# FPGA_U1_Auto.net
KiCad netlist of a schematic drawn in Altium Designer
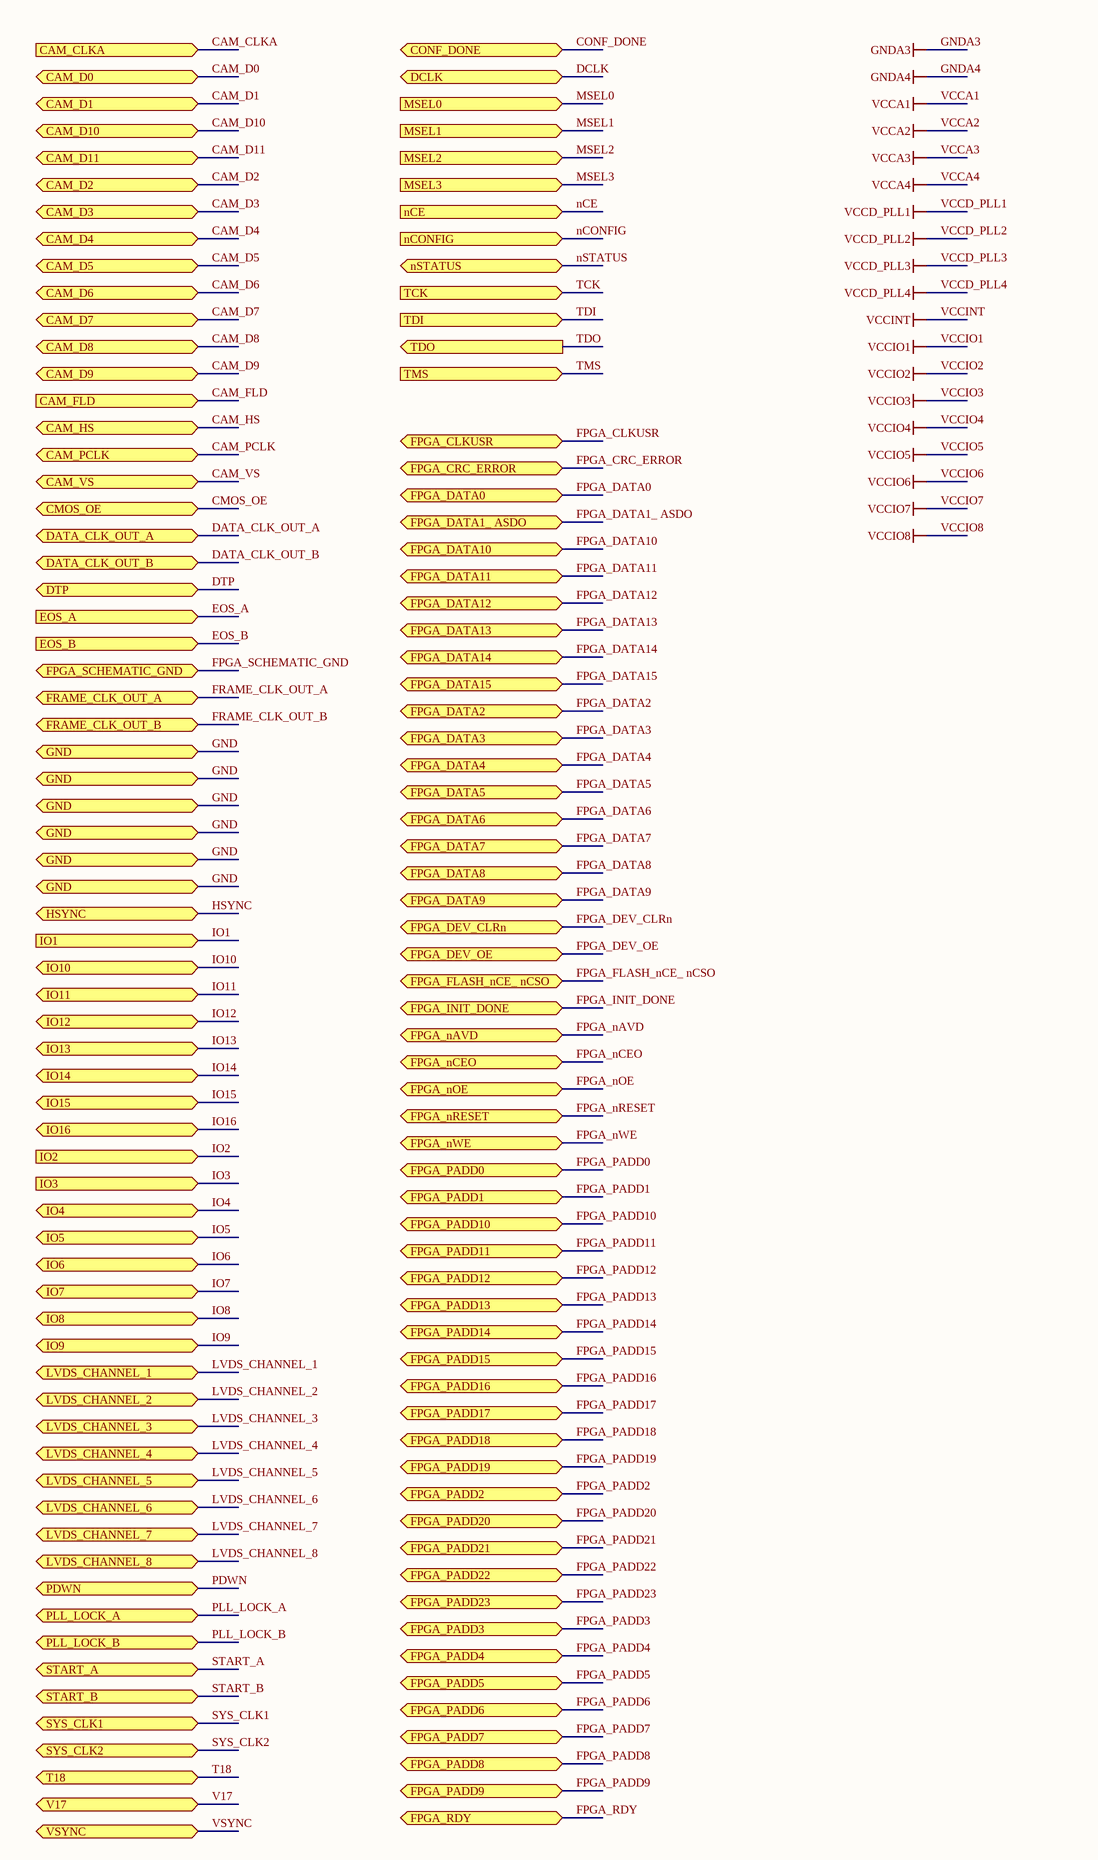
[diagram p0: FPGA_U1_Auto.SchDoc, top left]
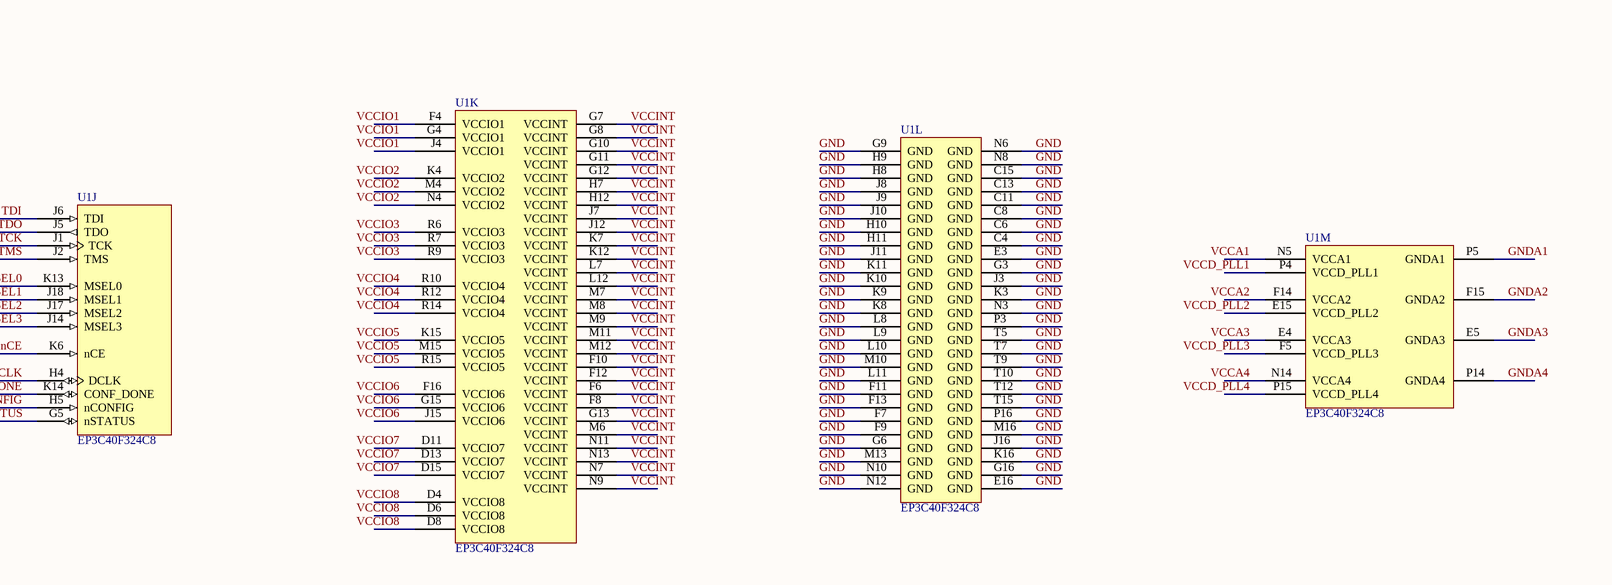
[diagram p1: FPGA_U1_Auto.SchDoc, top middle]
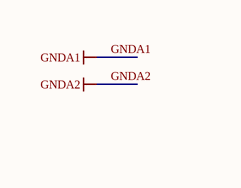
[diagram p2: FPGA_U1_Auto.SchDoc, bottom left]
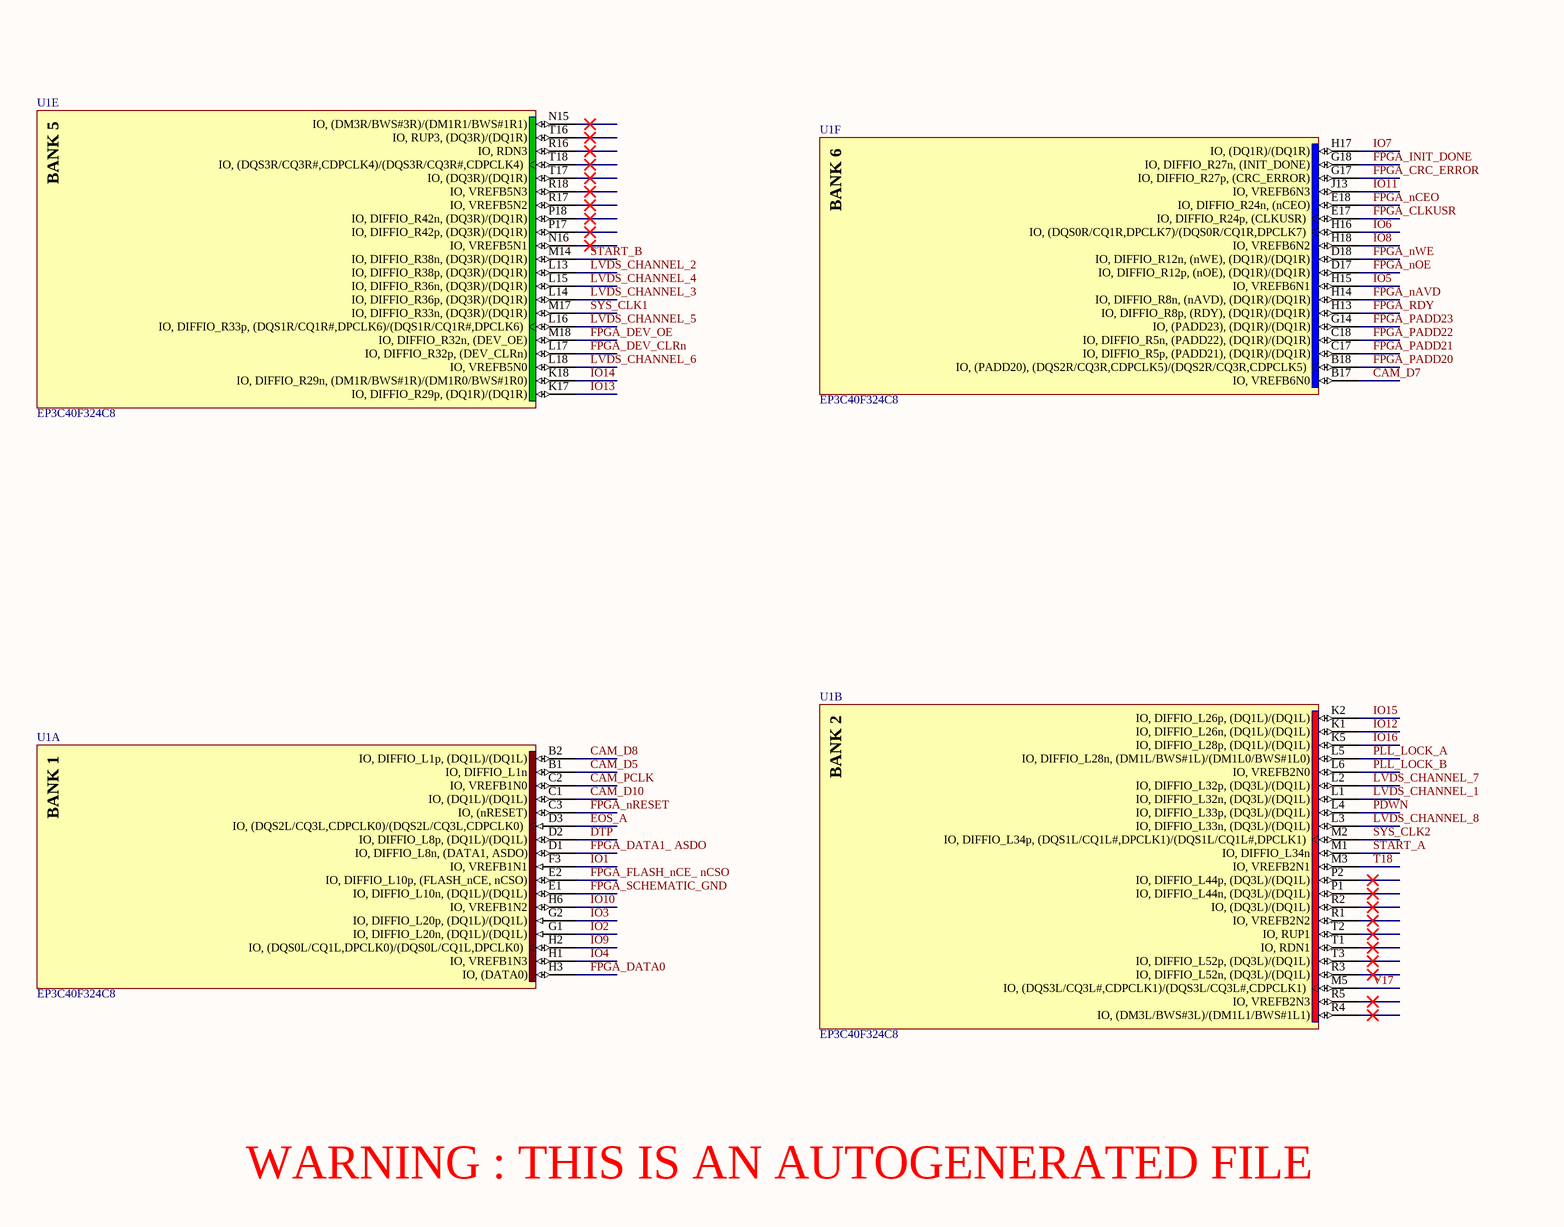
[diagram p3: FPGA_U1_Auto.SchDoc, bottom middle]
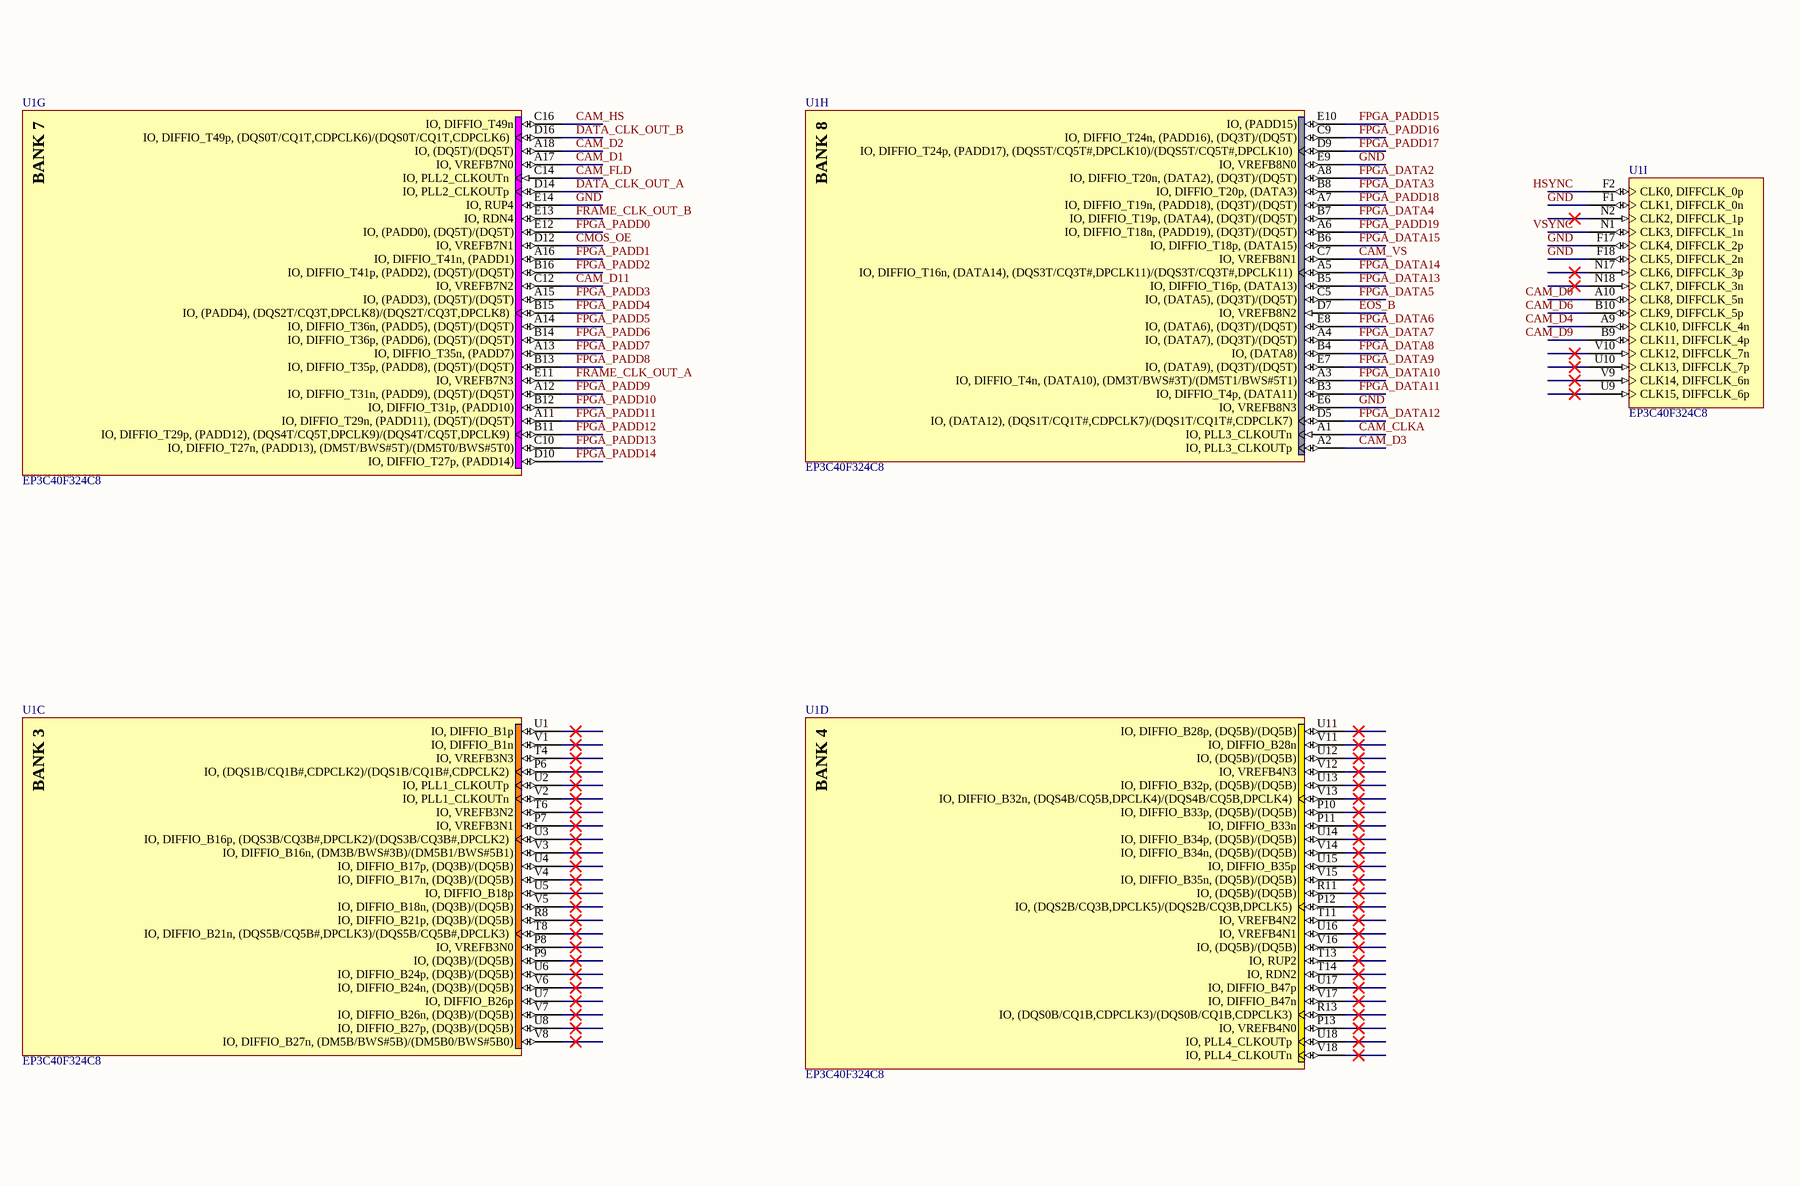
[diagram p4: FPGA_U1_Auto.SchDoc, bottom right]

(export (version "E")
  (design (tool "Eeschema 10.0.6"))
  (components
    (comp (ref "U1")
      (value "EP3C40F324C8")
      (footprint "FBGA324")
      (description "Cyclone III Family FPGA, 195 I/O Pins, 4 PLLs, 324-Pin FBGA, Speed Grade 8, Commercial Grade")
      (fields (field (name "PUBLISHER") "Altium Limited"))
      (libsource (lib "Altera Cyclone III") (part "EP3C40F324C8"))
    )
  )
  (nets
    (net (code "1") (name "/CAM_CLKA") (class "Default")
      (node (ref "U1") (pin "A1") (pinfunction "IO,_PLL3_CLKOUTn_A1") (pintype "bidirectional"))
    )
    (net (code "2") (name "/CAM_D0") (class "Default")
      (node (ref "U1") (pin "A10") (pinfunction "CLK8,_DIFFCLK_5n_A10") (pintype "input"))
    )
    (net (code "3") (name "/CAM_D1") (class "Default")
      (node (ref "U1") (pin "A17") (pinfunction "IO,_VREFB7N0_A17") (pintype "bidirectional"))
    )
    (net (code "4") (name "/CAM_D2") (class "Default")
      (node (ref "U1") (pin "A18") (pinfunction "IO,_(DQ5T)/(DQ5T)_A18") (pintype "bidirectional"))
    )
    (net (code "5") (name "/CAM_D3") (class "Default")
      (node (ref "U1") (pin "A2") (pinfunction "IO,_PLL3_CLKOUTp_A2") (pintype "bidirectional"))
    )
    (net (code "6") (name "/CAM_D4") (class "Default")
      (node (ref "U1") (pin "A9") (pinfunction "CLK10,_DIFFCLK_4n_A9") (pintype "input"))
    )
    (net (code "7") (name "/CAM_D5") (class "Default")
      (node (ref "U1") (pin "B1") (pinfunction "IO,_DIFFIO_L1n_B1") (pintype "bidirectional"))
    )
    (net (code "8") (name "/CAM_D6") (class "Default")
      (node (ref "U1") (pin "B10") (pinfunction "CLK9,_DIFFCLK_5p_B10") (pintype "input"))
    )
    (net (code "9") (name "/CAM_D7") (class "Default")
      (node (ref "U1") (pin "B17") (pinfunction "IO,_VREFB6N0_B17") (pintype "bidirectional"))
    )
    (net (code "10") (name "/CAM_D8") (class "Default")
      (node (ref "U1") (pin "B2") (pinfunction "IO,_DIFFIO_L1p,_(DQ1L)/(DQ1L)_B2") (pintype "bidirectional"))
    )
    (net (code "11") (name "/CAM_D9") (class "Default")
      (node (ref "U1") (pin "B9") (pinfunction "CLK11,_DIFFCLK_4p_B9") (pintype "input"))
    )
    (net (code "12") (name "/CAM_D10") (class "Default")
      (node (ref "U1") (pin "C1") (pinfunction "IO,_(DQ1L)/(DQ1L)_C1") (pintype "bidirectional"))
    )
    (net (code "13") (name "/CAM_D11") (class "Default")
      (node (ref "U1") (pin "C12") (pinfunction "IO,_VREFB7N2_C12") (pintype "bidirectional"))
    )
    (net (code "14") (name "/CAM_FLD") (class "Default")
      (node (ref "U1") (pin "C14") (pinfunction "IO,_PLL2_CLKOUTn_C14") (pintype "bidirectional"))
    )
    (net (code "15") (name "/CAM_HS") (class "Default")
      (node (ref "U1") (pin "C16") (pinfunction "IO,_DIFFIO_T49n_C16") (pintype "bidirectional"))
    )
    (net (code "16") (name "/CAM_PCLK") (class "Default")
      (node (ref "U1") (pin "C2") (pinfunction "IO,_VREFB1N0_C2") (pintype "bidirectional"))
    )
    (net (code "17") (name "/CAM_VS") (class "Default")
      (node (ref "U1") (pin "C7") (pinfunction "IO,_VREFB8N1_C7") (pintype "bidirectional"))
    )
    (net (code "18") (name "/CMOS_OE") (class "Default")
      (node (ref "U1") (pin "D12") (pinfunction "IO,_VREFB7N1_D12") (pintype "bidirectional"))
    )
    (net (code "19") (name "/CONF_DONE") (class "Default")
      (node (ref "U1") (pin "K14") (pinfunction "CONF_DONE_K14") (pintype "bidirectional"))
    )
    (net (code "20") (name "/DATA_CLK_OUT_A") (class "Default")
      (node (ref "U1") (pin "D14") (pinfunction "IO,_PLL2_CLKOUTp_D14") (pintype "bidirectional"))
    )
    (net (code "21") (name "/DATA_CLK_OUT_B") (class "Default")
      (node (ref "U1") (pin "D16") (pinfunction "IO,_DIFFIO_T49p,_(DQS0T/CQ1T,CDPCLK6)/(DQS0T/CQ1T,CDPCLK6)_D16") (pintype "bidirectional"))
    )
    (net (code "22") (name "/DCLK") (class "Default")
      (node (ref "U1") (pin "H4") (pinfunction "DCLK_H4") (pintype "bidirectional"))
    )
    (net (code "23") (name "/DTP") (class "Default")
      (node (ref "U1") (pin "D2") (pinfunction "IO,_DIFFIO_L8p,_(DQ1L)/(DQ1L)_D2") (pintype "bidirectional"))
    )
    (net (code "24") (name "/EOS_A") (class "Default")
      (node (ref "U1") (pin "D3") (pinfunction "IO,_(DQS2L/CQ3L,CDPCLK0)/(DQS2L/CQ3L,CDPCLK0)_D3") (pintype "bidirectional"))
    )
    (net (code "25") (name "/EOS_B") (class "Default")
      (node (ref "U1") (pin "D7") (pinfunction "IO,_VREFB8N2_D7") (pintype "bidirectional"))
    )
    (net (code "26") (name "/FPGA_CLKUSR") (class "Default")
      (node (ref "U1") (pin "E17") (pinfunction "IO,_DIFFIO_R24p,_(CLKUSR)_E17") (pintype "bidirectional"))
    )
    (net (code "27") (name "/FPGA_CRC_ERROR") (class "Default")
      (node (ref "U1") (pin "G17") (pinfunction "IO,_DIFFIO_R27p,_(CRC_ERROR)_G17") (pintype "bidirectional"))
    )
    (net (code "28") (name "/FPGA_DATA0") (class "Default")
      (node (ref "U1") (pin "H3") (pinfunction "IO,_(DATA0)_H3") (pintype "bidirectional"))
    )
    (net (code "29") (name "/FPGA_DATA1_ ASDO") (class "Default")
      (node (ref "U1") (pin "D1") (pinfunction "IO,_DIFFIO_L8n,_(DATA1,_ASDO)_D1") (pintype "bidirectional"))
    )
    (net (code "30") (name "/FPGA_DATA2") (class "Default")
      (node (ref "U1") (pin "A8") (pinfunction "IO,_DIFFIO_T20n,_(DATA2),_(DQ3T)/(DQ5T)_A8") (pintype "bidirectional"))
    )
    (net (code "31") (name "/FPGA_DATA3") (class "Default")
      (node (ref "U1") (pin "B8") (pinfunction "IO,_DIFFIO_T20p,_(DATA3)_B8") (pintype "bidirectional"))
    )
    (net (code "32") (name "/FPGA_DATA4") (class "Default")
      (node (ref "U1") (pin "B7") (pinfunction "IO,_DIFFIO_T19p,_(DATA4),_(DQ3T)/(DQ5T)_B7") (pintype "bidirectional"))
    )
    (net (code "33") (name "/FPGA_DATA5") (class "Default")
      (node (ref "U1") (pin "C5") (pinfunction "IO,_(DATA5),_(DQ3T)/(DQ5T)_C5") (pintype "bidirectional"))
    )
    (net (code "34") (name "/FPGA_DATA6") (class "Default")
      (node (ref "U1") (pin "E8") (pinfunction "IO,_(DATA6),_(DQ3T)/(DQ5T)_E8") (pintype "bidirectional"))
    )
    (net (code "35") (name "/FPGA_DATA7") (class "Default")
      (node (ref "U1") (pin "A4") (pinfunction "IO,_(DATA7),_(DQ3T)/(DQ5T)_A4") (pintype "bidirectional"))
    )
    (net (code "36") (name "/FPGA_DATA8") (class "Default")
      (node (ref "U1") (pin "B4") (pinfunction "IO,_(DATA8)_B4") (pintype "bidirectional"))
    )
    (net (code "37") (name "/FPGA_DATA9") (class "Default")
      (node (ref "U1") (pin "E7") (pinfunction "IO,_(DATA9),_(DQ3T)/(DQ5T)_E7") (pintype "bidirectional"))
    )
    (net (code "38") (name "/FPGA_DATA10") (class "Default")
      (node (ref "U1") (pin "A3") (pinfunction "IO,_DIFFIO_T4n,_(DATA10),_(DM3T/BWS#3T)/(DM5T1/BWS#5T1)_A3") (pintype "bidirectional"))
    )
    (net (code "39") (name "/FPGA_DATA11") (class "Default")
      (node (ref "U1") (pin "B3") (pinfunction "IO,_DIFFIO_T4p,_(DATA11)_B3") (pintype "bidirectional"))
    )
    (net (code "40") (name "/FPGA_DATA12") (class "Default")
      (node (ref "U1") (pin "D5") (pinfunction "IO,_(DATA12),_(DQS1T/CQ1T#,CDPCLK7)/(DQS1T/CQ1T#,CDPCLK7)_D5") (pintype "bidirectional"))
    )
    (net (code "41") (name "/FPGA_DATA13") (class "Default")
      (node (ref "U1") (pin "B5") (pinfunction "IO,_DIFFIO_T16p,_(DATA13)_B5") (pintype "bidirectional"))
    )
    (net (code "42") (name "/FPGA_DATA14") (class "Default")
      (node (ref "U1") (pin "A5") (pinfunction "IO,_DIFFIO_T16n,_(DATA14),_(DQS3T/CQ3T#,DPCLK11)/(DQS3T/CQ3T#,DPCLK11)_A5") (pintype "bidirectional"))
    )
    (net (code "43") (name "/FPGA_DATA15") (class "Default")
      (node (ref "U1") (pin "B6") (pinfunction "IO,_DIFFIO_T18p,_(DATA15)_B6") (pintype "bidirectional"))
    )
    (net (code "44") (name "/FPGA_DEV_CLRn") (class "Default")
      (node (ref "U1") (pin "L17") (pinfunction "IO,_DIFFIO_R32p,_(DEV_CLRn)_L17") (pintype "bidirectional"))
    )
    (net (code "45") (name "/FPGA_DEV_OE") (class "Default")
      (node (ref "U1") (pin "M18") (pinfunction "IO,_DIFFIO_R32n,_(DEV_OE)_M18") (pintype "bidirectional"))
    )
    (net (code "46") (name "/FPGA_FLASH_nCE_ nCSO") (class "Default")
      (node (ref "U1") (pin "E2") (pinfunction "IO,_DIFFIO_L10p,_(FLASH_nCE,_nCSO)_E2") (pintype "bidirectional"))
    )
    (net (code "47") (name "/FPGA_INIT_DONE") (class "Default")
      (node (ref "U1") (pin "G18") (pinfunction "IO,_DIFFIO_R27n,_(INIT_DONE)_G18") (pintype "bidirectional"))
    )
    (net (code "48") (name "/FPGA_PADD0") (class "Default")
      (node (ref "U1") (pin "E12") (pinfunction "IO,_(PADD0),_(DQ5T)/(DQ5T)_E12") (pintype "bidirectional"))
    )
    (net (code "49") (name "/FPGA_PADD1") (class "Default")
      (node (ref "U1") (pin "A16") (pinfunction "IO,_DIFFIO_T41n,_(PADD1)_A16") (pintype "bidirectional"))
    )
    (net (code "50") (name "/FPGA_PADD2") (class "Default")
      (node (ref "U1") (pin "B16") (pinfunction "IO,_DIFFIO_T41p,_(PADD2),_(DQ5T)/(DQ5T)_B16") (pintype "bidirectional"))
    )
    (net (code "51") (name "/FPGA_PADD3") (class "Default")
      (node (ref "U1") (pin "A15") (pinfunction "IO,_(PADD3),_(DQ5T)/(DQ5T)_A15") (pintype "bidirectional"))
    )
    (net (code "52") (name "/FPGA_PADD4") (class "Default")
      (node (ref "U1") (pin "B15") (pinfunction "IO,_(PADD4),_(DQS2T/CQ3T,DPCLK8)/(DQS2T/CQ3T,DPCLK8)_B15") (pintype "bidirectional"))
    )
    (net (code "53") (name "/FPGA_PADD5") (class "Default")
      (node (ref "U1") (pin "A14") (pinfunction "IO,_DIFFIO_T36n,_(PADD5),_(DQ5T)/(DQ5T)_A14") (pintype "bidirectional"))
    )
    (net (code "54") (name "/FPGA_PADD6") (class "Default")
      (node (ref "U1") (pin "B14") (pinfunction "IO,_DIFFIO_T36p,_(PADD6),_(DQ5T)/(DQ5T)_B14") (pintype "bidirectional"))
    )
    (net (code "55") (name "/FPGA_PADD7") (class "Default")
      (node (ref "U1") (pin "A13") (pinfunction "IO,_DIFFIO_T35n,_(PADD7)_A13") (pintype "bidirectional"))
    )
    (net (code "56") (name "/FPGA_PADD8") (class "Default")
      (node (ref "U1") (pin "B13") (pinfunction "IO,_DIFFIO_T35p,_(PADD8),_(DQ5T)/(DQ5T)_B13") (pintype "bidirectional"))
    )
    (net (code "57") (name "/FPGA_PADD9") (class "Default")
      (node (ref "U1") (pin "A12") (pinfunction "IO,_DIFFIO_T31n,_(PADD9),_(DQ5T)/(DQ5T)_A12") (pintype "bidirectional"))
    )
    (net (code "58") (name "/FPGA_PADD10") (class "Default")
      (node (ref "U1") (pin "B12") (pinfunction "IO,_DIFFIO_T31p,_(PADD10)_B12") (pintype "bidirectional"))
    )
    (net (code "59") (name "/FPGA_PADD11") (class "Default")
      (node (ref "U1") (pin "A11") (pinfunction "IO,_DIFFIO_T29n,_(PADD11),_(DQ5T)/(DQ5T)_A11") (pintype "bidirectional"))
    )
    (net (code "60") (name "/FPGA_PADD12") (class "Default")
      (node (ref "U1") (pin "B11") (pinfunction "IO,_DIFFIO_T29p,_(PADD12),_(DQS4T/CQ5T,DPCLK9)/(DQS4T/CQ5T,DPCLK9)_B11") (pintype "bidirectional"))
    )
    (net (code "61") (name "/FPGA_PADD13") (class "Default")
      (node (ref "U1") (pin "C10") (pinfunction "IO,_DIFFIO_T27n,_(PADD13),_(DM5T/BWS#5T)/(DM5T0/BWS#5T0)_C10") (pintype "bidirectional"))
    )
    (net (code "62") (name "/FPGA_PADD14") (class "Default")
      (node (ref "U1") (pin "D10") (pinfunction "IO,_DIFFIO_T27p,_(PADD14)_D10") (pintype "bidirectional"))
    )
    (net (code "63") (name "/FPGA_PADD15") (class "Default")
      (node (ref "U1") (pin "E10") (pinfunction "IO,_(PADD15)_E10") (pintype "bidirectional"))
    )
    (net (code "64") (name "/FPGA_PADD16") (class "Default")
      (node (ref "U1") (pin "C9") (pinfunction "IO,_DIFFIO_T24n,_(PADD16),_(DQ3T)/(DQ5T)_C9") (pintype "bidirectional"))
    )
    (net (code "65") (name "/FPGA_PADD17") (class "Default")
      (node (ref "U1") (pin "D9") (pinfunction "IO,_DIFFIO_T24p,_(PADD17),_(DQS5T/CQ5T#,DPCLK10)/(DQS5T/CQ5T#,DPCLK10)_D9") (pintype "bidirectional"))
    )
    (net (code "66") (name "/FPGA_PADD18") (class "Default")
      (node (ref "U1") (pin "A7") (pinfunction "IO,_DIFFIO_T19n,_(PADD18),_(DQ3T)/(DQ5T)_A7") (pintype "bidirectional"))
    )
    (net (code "67") (name "/FPGA_PADD19") (class "Default")
      (node (ref "U1") (pin "A6") (pinfunction "IO,_DIFFIO_T18n,_(PADD19),_(DQ3T)/(DQ5T)_A6") (pintype "bidirectional"))
    )
    (net (code "68") (name "/FPGA_PADD20") (class "Default")
      (node (ref "U1") (pin "B18") (pinfunction "IO,_(PADD20),_(DQS2R/CQ3R,CDPCLK5)/(DQS2R/CQ3R,CDPCLK5)_B18") (pintype "bidirectional"))
    )
    (net (code "69") (name "/FPGA_PADD21") (class "Default")
      (node (ref "U1") (pin "C17") (pinfunction "IO,_DIFFIO_R5p,_(PADD21),_(DQ1R)/(DQ1R)_C17") (pintype "bidirectional"))
    )
    (net (code "70") (name "/FPGA_PADD22") (class "Default")
      (node (ref "U1") (pin "C18") (pinfunction "IO,_DIFFIO_R5n,_(PADD22),_(DQ1R)/(DQ1R)_C18") (pintype "bidirectional"))
    )
    (net (code "71") (name "/FPGA_PADD23") (class "Default")
      (node (ref "U1") (pin "G14") (pinfunction "IO,_(PADD23),_(DQ1R)/(DQ1R)_G14") (pintype "bidirectional"))
    )
    (net (code "72") (name "/FPGA_RDY") (class "Default")
      (node (ref "U1") (pin "H13") (pinfunction "IO,_DIFFIO_R8p,_(RDY),_(DQ1R)/(DQ1R)_H13") (pintype "bidirectional"))
    )
    (net (code "73") (name "/FPGA_SCHEMATIC_GND") (class "Default")
      (node (ref "U1") (pin "E1") (pinfunction "IO,_DIFFIO_L10n,_(DQ1L)/(DQ1L)_E1") (pintype "bidirectional"))
    )
    (net (code "74") (name "/FPGA_nAVD") (class "Default")
      (node (ref "U1") (pin "H14") (pinfunction "IO,_DIFFIO_R8n,_(nAVD),_(DQ1R)/(DQ1R)_H14") (pintype "bidirectional"))
    )
    (net (code "75") (name "/FPGA_nCEO") (class "Default")
      (node (ref "U1") (pin "E18") (pinfunction "IO,_DIFFIO_R24n,_(nCEO)_E18") (pintype "bidirectional"))
    )
    (net (code "76") (name "/FPGA_nOE") (class "Default")
      (node (ref "U1") (pin "D17") (pinfunction "IO,_DIFFIO_R12p,_(nOE),_(DQ1R)/(DQ1R)_D17") (pintype "bidirectional"))
    )
    (net (code "77") (name "/FPGA_nRESET") (class "Default")
      (node (ref "U1") (pin "C3") (pinfunction "IO,_(nRESET)_C3") (pintype "bidirectional"))
    )
    (net (code "78") (name "/FPGA_nWE") (class "Default")
      (node (ref "U1") (pin "D18") (pinfunction "IO,_DIFFIO_R12n,_(nWE),_(DQ1R)/(DQ1R)_D18") (pintype "bidirectional"))
    )
    (net (code "79") (name "/FRAME_CLK_OUT_A") (class "Default")
      (node (ref "U1") (pin "E11") (pinfunction "IO,_VREFB7N3_E11") (pintype "bidirectional"))
    )
    (net (code "80") (name "/FRAME_CLK_OUT_B") (class "Default")
      (node (ref "U1") (pin "E13") (pinfunction "IO,_RDN4_E13") (pintype "bidirectional"))
    )
    (net (code "81") (name "/GND") (class "Default")
      (node (ref "U1") (pin "C11") (pinfunction "GND_C11") (pintype "power_in"))
      (node (ref "U1") (pin "C13") (pinfunction "GND_C13") (pintype "power_in"))
      (node (ref "U1") (pin "C15") (pinfunction "GND_C15") (pintype "power_in"))
      (node (ref "U1") (pin "C4") (pinfunction "GND_C4") (pintype "power_in"))
      (node (ref "U1") (pin "C6") (pinfunction "GND_C6") (pintype "power_in"))
      (node (ref "U1") (pin "C8") (pinfunction "GND_C8") (pintype "power_in"))
      (node (ref "U1") (pin "E14") (pinfunction "IO,_RUP4_E14") (pintype "bidirectional"))
      (node (ref "U1") (pin "E16") (pinfunction "GND_E16") (pintype "power_in"))
      (node (ref "U1") (pin "E3") (pinfunction "GND_E3") (pintype "power_in"))
      (node (ref "U1") (pin "E6") (pinfunction "IO,_VREFB8N3_E6") (pintype "bidirectional"))
      (node (ref "U1") (pin "E9") (pinfunction "IO,_VREFB8N0_E9") (pintype "bidirectional"))
      (node (ref "U1") (pin "F1") (pinfunction "CLK1,_DIFFCLK_0n_F1") (pintype "input"))
      (node (ref "U1") (pin "F11") (pinfunction "GND_F11") (pintype "power_in"))
      (node (ref "U1") (pin "F13") (pinfunction "GND_F13") (pintype "power_in"))
      (node (ref "U1") (pin "F17") (pinfunction "CLK4,_DIFFCLK_2p_F17") (pintype "input"))
      (node (ref "U1") (pin "F18") (pinfunction "CLK5,_DIFFCLK_2n_F18") (pintype "input"))
      (node (ref "U1") (pin "F7") (pinfunction "GND_F7") (pintype "power_in"))
      (node (ref "U1") (pin "F9") (pinfunction "GND_F9") (pintype "power_in"))
      (node (ref "U1") (pin "G16") (pinfunction "GND_G16") (pintype "power_in"))
      (node (ref "U1") (pin "G3") (pinfunction "GND_G3") (pintype "power_in"))
      (node (ref "U1") (pin "G6") (pinfunction "GND_G6") (pintype "power_in"))
      (node (ref "U1") (pin "G9") (pinfunction "GND_G9") (pintype "power_in"))
      (node (ref "U1") (pin "H10") (pinfunction "GND_H10") (pintype "power_in"))
      (node (ref "U1") (pin "H11") (pinfunction "GND_H11") (pintype "power_in"))
      (node (ref "U1") (pin "H8") (pinfunction "GND_H8") (pintype "power_in"))
      (node (ref "U1") (pin "H9") (pinfunction "GND_H9") (pintype "power_in"))
      (node (ref "U1") (pin "J10") (pinfunction "GND_J10") (pintype "power_in"))
      (node (ref "U1") (pin "J11") (pinfunction "GND_J11") (pintype "power_in"))
      (node (ref "U1") (pin "J16") (pinfunction "GND_J16") (pintype "power_in"))
      (node (ref "U1") (pin "J3") (pinfunction "GND_J3") (pintype "power_in"))
      (node (ref "U1") (pin "J8") (pinfunction "GND_J8") (pintype "power_in"))
      (node (ref "U1") (pin "J9") (pinfunction "GND_J9") (pintype "power_in"))
      (node (ref "U1") (pin "K10") (pinfunction "GND_K10") (pintype "power_in"))
      (node (ref "U1") (pin "K11") (pinfunction "GND_K11") (pintype "power_in"))
      (node (ref "U1") (pin "K16") (pinfunction "GND_K16") (pintype "power_in"))
      (node (ref "U1") (pin "K3") (pinfunction "GND_K3") (pintype "power_in"))
      (node (ref "U1") (pin "K8") (pinfunction "GND_K8") (pintype "power_in"))
      (node (ref "U1") (pin "K9") (pinfunction "GND_K9") (pintype "power_in"))
      (node (ref "U1") (pin "L10") (pinfunction "GND_L10") (pintype "power_in"))
      (node (ref "U1") (pin "L11") (pinfunction "GND_L11") (pintype "power_in"))
      (node (ref "U1") (pin "L8") (pinfunction "GND_L8") (pintype "power_in"))
      (node (ref "U1") (pin "L9") (pinfunction "GND_L9") (pintype "power_in"))
      (node (ref "U1") (pin "M10") (pinfunction "GND_M10") (pintype "power_in"))
      (node (ref "U1") (pin "M13") (pinfunction "GND_M13") (pintype "power_in"))
      (node (ref "U1") (pin "M16") (pinfunction "GND_M16") (pintype "power_in"))
      (node (ref "U1") (pin "N10") (pinfunction "GND_N10") (pintype "power_in"))
      (node (ref "U1") (pin "N12") (pinfunction "GND_N12") (pintype "power_in"))
      (node (ref "U1") (pin "N3") (pinfunction "GND_N3") (pintype "power_in"))
      (node (ref "U1") (pin "N6") (pinfunction "GND_N6") (pintype "power_in"))
      (node (ref "U1") (pin "N8") (pinfunction "GND_N8") (pintype "power_in"))
      (node (ref "U1") (pin "P16") (pinfunction "GND_P16") (pintype "power_in"))
      (node (ref "U1") (pin "P3") (pinfunction "GND_P3") (pintype "power_in"))
      (node (ref "U1") (pin "T10") (pinfunction "GND_T10") (pintype "power_in"))
      (node (ref "U1") (pin "T12") (pinfunction "GND_T12") (pintype "power_in"))
      (node (ref "U1") (pin "T15") (pinfunction "GND_T15") (pintype "power_in"))
      (node (ref "U1") (pin "T5") (pinfunction "GND_T5") (pintype "power_in"))
      (node (ref "U1") (pin "T7") (pinfunction "GND_T7") (pintype "power_in"))
      (node (ref "U1") (pin "T9") (pinfunction "GND_T9") (pintype "power_in"))
    )
    (net (code "82") (name "/HSYNC") (class "Default")
      (node (ref "U1") (pin "F2") (pinfunction "CLK0,_DIFFCLK_0p_F2") (pintype "input"))
    )
    (net (code "83") (name "/IO1") (class "Default")
      (node (ref "U1") (pin "F3") (pinfunction "IO,_VREFB1N1_F3") (pintype "bidirectional"))
    )
    (net (code "84") (name "/IO2") (class "Default")
      (node (ref "U1") (pin "G1") (pinfunction "IO,_DIFFIO_L20n,_(DQ1L)/(DQ1L)_G1") (pintype "bidirectional"))
    )
    (net (code "85") (name "/IO3") (class "Default")
      (node (ref "U1") (pin "G2") (pinfunction "IO,_DIFFIO_L20p,_(DQ1L)/(DQ1L)_G2") (pintype "bidirectional"))
    )
    (net (code "86") (name "/IO4") (class "Default")
      (node (ref "U1") (pin "H1") (pinfunction "IO,_VREFB1N3_H1") (pintype "bidirectional"))
    )
    (net (code "87") (name "/IO5") (class "Default")
      (node (ref "U1") (pin "H15") (pinfunction "IO,_VREFB6N1_H15") (pintype "bidirectional"))
    )
    (net (code "88") (name "/IO6") (class "Default")
      (node (ref "U1") (pin "H16") (pinfunction "IO,_(DQS0R/CQ1R,DPCLK7)/(DQS0R/CQ1R,DPCLK7)_H16") (pintype "bidirectional"))
    )
    (net (code "89") (name "/IO7") (class "Default")
      (node (ref "U1") (pin "H17") (pinfunction "IO,_(DQ1R)/(DQ1R)_H17") (pintype "bidirectional"))
    )
    (net (code "90") (name "/IO8") (class "Default")
      (node (ref "U1") (pin "H18") (pinfunction "IO,_VREFB6N2_H18") (pintype "bidirectional"))
    )
    (net (code "91") (name "/IO9") (class "Default")
      (node (ref "U1") (pin "H2") (pinfunction "IO,_(DQS0L/CQ1L,DPCLK0)/(DQS0L/CQ1L,DPCLK0)_H2") (pintype "bidirectional"))
    )
    (net (code "92") (name "/IO10") (class "Default")
      (node (ref "U1") (pin "H6") (pinfunction "IO,_VREFB1N2_H6") (pintype "bidirectional"))
    )
    (net (code "93") (name "/IO11") (class "Default")
      (node (ref "U1") (pin "J13") (pinfunction "IO,_VREFB6N3_J13") (pintype "bidirectional"))
    )
    (net (code "94") (name "/IO12") (class "Default")
      (node (ref "U1") (pin "K1") (pinfunction "IO,_DIFFIO_L26n,_(DQ1L)/(DQ1L)_K1") (pintype "bidirectional"))
    )
    (net (code "95") (name "/IO13") (class "Default")
      (node (ref "U1") (pin "K17") (pinfunction "IO,_DIFFIO_R29p,_(DQ1R)/(DQ1R)_K17") (pintype "bidirectional"))
    )
    (net (code "96") (name "/IO14") (class "Default")
      (node (ref "U1") (pin "K18") (pinfunction "IO,_DIFFIO_R29n,_(DM1R/BWS#1R)/(DM1R0/BWS#1R0)_K18") (pintype "bidirectional"))
    )
    (net (code "97") (name "/IO15") (class "Default")
      (node (ref "U1") (pin "K2") (pinfunction "IO,_DIFFIO_L26p,_(DQ1L)/(DQ1L)_K2") (pintype "bidirectional"))
    )
    (net (code "98") (name "/IO16") (class "Default")
      (node (ref "U1") (pin "K5") (pinfunction "IO,_DIFFIO_L28p,_(DQ1L)/(DQ1L)_K5") (pintype "bidirectional"))
    )
    (net (code "99") (name "/LVDS_CHANNEL_1") (class "Default")
      (node (ref "U1") (pin "L1") (pinfunction "IO,_DIFFIO_L32n,_(DQ3L)/(DQ1L)_L1") (pintype "bidirectional"))
    )
    (net (code "100") (name "/LVDS_CHANNEL_2") (class "Default")
      (node (ref "U1") (pin "L13") (pinfunction "IO,_DIFFIO_R38p,_(DQ3R)/(DQ1R)_L13") (pintype "bidirectional"))
    )
    (net (code "101") (name "/LVDS_CHANNEL_3") (class "Default")
      (node (ref "U1") (pin "L14") (pinfunction "IO,_DIFFIO_R36p,_(DQ3R)/(DQ1R)_L14") (pintype "bidirectional"))
    )
    (net (code "102") (name "/LVDS_CHANNEL_4") (class "Default")
      (node (ref "U1") (pin "L15") (pinfunction "IO,_DIFFIO_R36n,_(DQ3R)/(DQ1R)_L15") (pintype "bidirectional"))
    )
    (net (code "103") (name "/LVDS_CHANNEL_5") (class "Default")
      (node (ref "U1") (pin "L16") (pinfunction "IO,_DIFFIO_R33p,_(DQS1R/CQ1R#,DPCLK6)/(DQS1R/CQ1R#,DPCLK6)_L16") (pintype "bidirectional"))
    )
    (net (code "104") (name "/LVDS_CHANNEL_6") (class "Default")
      (node (ref "U1") (pin "L18") (pinfunction "IO,_VREFB5N0_L18") (pintype "bidirectional"))
    )
    (net (code "105") (name "/LVDS_CHANNEL_7") (class "Default")
      (node (ref "U1") (pin "L2") (pinfunction "IO,_DIFFIO_L32p,_(DQ3L)/(DQ1L)_L2") (pintype "bidirectional"))
    )
    (net (code "106") (name "/LVDS_CHANNEL_8") (class "Default")
      (node (ref "U1") (pin "L3") (pinfunction "IO,_DIFFIO_L33n,_(DQ3L)/(DQ1L)_L3") (pintype "bidirectional"))
    )
    (net (code "107") (name "/MSEL0") (class "Default")
      (node (ref "U1") (pin "K13") (pinfunction "MSEL0_K13") (pintype "input"))
    )
    (net (code "108") (name "/MSEL1") (class "Default")
      (node (ref "U1") (pin "J18") (pinfunction "MSEL1_J18") (pintype "input"))
    )
    (net (code "109") (name "/MSEL2") (class "Default")
      (node (ref "U1") (pin "J17") (pinfunction "MSEL2_J17") (pintype "input"))
    )
    (net (code "110") (name "/MSEL3") (class "Default")
      (node (ref "U1") (pin "J14") (pinfunction "MSEL3_J14") (pintype "input"))
    )
    (net (code "111") (name "/PDWN") (class "Default")
      (node (ref "U1") (pin "L4") (pinfunction "IO,_DIFFIO_L33p,_(DQ3L)/(DQ1L)_L4") (pintype "bidirectional"))
    )
    (net (code "112") (name "/PLL_LOCK_A") (class "Default")
      (node (ref "U1") (pin "L5") (pinfunction "IO,_DIFFIO_L28n,_(DM1L/BWS#1L)/(DM1L0/BWS#1L0)_L5") (pintype "bidirectional"))
    )
    (net (code "113") (name "/PLL_LOCK_B") (class "Default")
      (node (ref "U1") (pin "L6") (pinfunction "IO,_VREFB2N0_L6") (pintype "bidirectional"))
    )
    (net (code "114") (name "/START_A") (class "Default")
      (node (ref "U1") (pin "M1") (pinfunction "IO,_DIFFIO_L34n_M1") (pintype "bidirectional"))
    )
    (net (code "115") (name "/START_B") (class "Default")
      (node (ref "U1") (pin "M14") (pinfunction "IO,_DIFFIO_R38n,_(DQ3R)/(DQ1R)_M14") (pintype "bidirectional"))
    )
    (net (code "116") (name "/SYS_CLK1") (class "Default")
      (node (ref "U1") (pin "M17") (pinfunction "IO,_DIFFIO_R33n,_(DQ3R)/(DQ1R)_M17") (pintype "bidirectional"))
    )
    (net (code "117") (name "/SYS_CLK2") (class "Default")
      (node (ref "U1") (pin "M2") (pinfunction "IO,_DIFFIO_L34p,_(DQS1L/CQ1L#,DPCLK1)/(DQS1L/CQ1L#,DPCLK1)_M2") (pintype "bidirectional"))
    )
    (net (code "118") (name "/T18") (class "Default")
      (node (ref "U1") (pin "M3") (pinfunction "IO,_VREFB2N1_M3") (pintype "bidirectional"))
    )
    (net (code "119") (name "/TCK") (class "Default")
      (node (ref "U1") (pin "J1") (pinfunction "TCK_J1") (pintype "input"))
    )
    (net (code "120") (name "/TDI") (class "Default")
      (node (ref "U1") (pin "J6") (pinfunction "TDI_J6") (pintype "input"))
    )
    (net (code "121") (name "/TDO") (class "Default")
      (node (ref "U1") (pin "J5") (pinfunction "TDO_J5") (pintype "output"))
    )
    (net (code "122") (name "/TMS") (class "Default")
      (node (ref "U1") (pin "J2") (pinfunction "TMS_J2") (pintype "input"))
    )
    (net (code "123") (name "/V17") (class "Default")
      (node (ref "U1") (pin "M5") (pinfunction "IO,_(DQS3L/CQ3L#,CDPCLK1)/(DQS3L/CQ3L#,CDPCLK1)_M5") (pintype "bidirectional"))
    )
    (net (code "124") (name "/VSYNC") (class "Default")
      (node (ref "U1") (pin "N1") (pinfunction "CLK3,_DIFFCLK_1n_N1") (pintype "input"))
    )
    (net (code "125") (name "/nCE") (class "Default")
      (node (ref "U1") (pin "K6") (pinfunction "nCE_K6") (pintype "input"))
    )
    (net (code "126") (name "/nCONFIG") (class "Default")
      (node (ref "U1") (pin "H5") (pinfunction "nCONFIG_H5") (pintype "input"))
    )
    (net (code "127") (name "/nSTATUS") (class "Default")
      (node (ref "U1") (pin "G5") (pinfunction "nSTATUS_G5") (pintype "bidirectional"))
    )
    (net (code "128") (name "GNDA1") (class "Default")
      (node (ref "U1") (pin "P5") (pinfunction "GNDA1_P5") (pintype "power_in"))
    )
    (net (code "129") (name "GNDA2") (class "Default")
      (node (ref "U1") (pin "F15") (pinfunction "GNDA2_F15") (pintype "power_in"))
    )
    (net (code "130") (name "GNDA3") (class "Default")
      (node (ref "U1") (pin "E5") (pinfunction "GNDA3_E5") (pintype "power_in"))
    )
    (net (code "131") (name "GNDA4") (class "Default")
      (node (ref "U1") (pin "P14") (pinfunction "GNDA4_P14") (pintype "power_in"))
    )
    (net (code "132") (name "VCCA1") (class "Default")
      (node (ref "U1") (pin "N5") (pinfunction "VCCA1_N5") (pintype "power_in"))
    )
    (net (code "133") (name "VCCA2") (class "Default")
      (node (ref "U1") (pin "F14") (pinfunction "VCCA2_F14") (pintype "power_in"))
    )
    (net (code "134") (name "VCCA3") (class "Default")
      (node (ref "U1") (pin "E4") (pinfunction "VCCA3_E4") (pintype "power_in"))
    )
    (net (code "135") (name "VCCA4") (class "Default")
      (node (ref "U1") (pin "N14") (pinfunction "VCCA4_N14") (pintype "power_in"))
    )
    (net (code "136") (name "VCCD_PLL1") (class "Default")
      (node (ref "U1") (pin "P4") (pinfunction "VCCD_PLL1_P4") (pintype "power_in"))
    )
    (net (code "137") (name "VCCD_PLL2") (class "Default")
      (node (ref "U1") (pin "E15") (pinfunction "VCCD_PLL2_E15") (pintype "power_in"))
    )
    (net (code "138") (name "VCCD_PLL3") (class "Default")
      (node (ref "U1") (pin "F5") (pinfunction "VCCD_PLL3_F5") (pintype "power_in"))
    )
    (net (code "139") (name "VCCD_PLL4") (class "Default")
      (node (ref "U1") (pin "P15") (pinfunction "VCCD_PLL4_P15") (pintype "power_in"))
    )
    (net (code "140") (name "VCCINT") (class "Default")
      (node (ref "U1") (pin "F10") (pinfunction "VCCINT_F10") (pintype "power_in"))
      (node (ref "U1") (pin "F12") (pinfunction "VCCINT_F12") (pintype "power_in"))
      (node (ref "U1") (pin "F6") (pinfunction "VCCINT_F6") (pintype "power_in"))
      (node (ref "U1") (pin "F8") (pinfunction "VCCINT_F8") (pintype "power_in"))
      (node (ref "U1") (pin "G10") (pinfunction "VCCINT_G10") (pintype "power_in"))
      (node (ref "U1") (pin "G11") (pinfunction "VCCINT_G11") (pintype "power_in"))
      (node (ref "U1") (pin "G12") (pinfunction "VCCINT_G12") (pintype "power_in"))
      (node (ref "U1") (pin "G13") (pinfunction "VCCINT_G13") (pintype "power_in"))
      (node (ref "U1") (pin "G7") (pinfunction "VCCINT_G7") (pintype "power_in"))
      (node (ref "U1") (pin "G8") (pinfunction "VCCINT_G8") (pintype "power_in"))
      (node (ref "U1") (pin "H12") (pinfunction "VCCINT_H12") (pintype "power_in"))
      (node (ref "U1") (pin "H7") (pinfunction "VCCINT_H7") (pintype "power_in"))
      (node (ref "U1") (pin "J12") (pinfunction "VCCINT_J12") (pintype "power_in"))
      (node (ref "U1") (pin "J7") (pinfunction "VCCINT_J7") (pintype "power_in"))
      (node (ref "U1") (pin "K12") (pinfunction "VCCINT_K12") (pintype "power_in"))
      (node (ref "U1") (pin "K7") (pinfunction "VCCINT_K7") (pintype "power_in"))
      (node (ref "U1") (pin "L12") (pinfunction "VCCINT_L12") (pintype "power_in"))
      (node (ref "U1") (pin "L7") (pinfunction "VCCINT_L7") (pintype "power_in"))
      (node (ref "U1") (pin "M11") (pinfunction "VCCINT_M11") (pintype "power_in"))
      (node (ref "U1") (pin "M12") (pinfunction "VCCINT_M12") (pintype "power_in"))
      (node (ref "U1") (pin "M6") (pinfunction "VCCINT_M6") (pintype "power_in"))
      (node (ref "U1") (pin "M7") (pinfunction "VCCINT_M7") (pintype "power_in"))
      (node (ref "U1") (pin "M8") (pinfunction "VCCINT_M8") (pintype "power_in"))
      (node (ref "U1") (pin "M9") (pinfunction "VCCINT_M9") (pintype "power_in"))
      (node (ref "U1") (pin "N11") (pinfunction "VCCINT_N11") (pintype "power_in"))
      (node (ref "U1") (pin "N13") (pinfunction "VCCINT_N13") (pintype "power_in"))
      (node (ref "U1") (pin "N7") (pinfunction "VCCINT_N7") (pintype "power_in"))
      (node (ref "U1") (pin "N9") (pinfunction "VCCINT_N9") (pintype "power_in"))
    )
    (net (code "141") (name "VCCIO1") (class "Default")
      (node (ref "U1") (pin "F4") (pinfunction "VCCIO1_F4") (pintype "power_in"))
      (node (ref "U1") (pin "G4") (pinfunction "VCCIO1_G4") (pintype "power_in"))
      (node (ref "U1") (pin "J4") (pinfunction "VCCIO1_J4") (pintype "power_in"))
    )
    (net (code "142") (name "VCCIO2") (class "Default")
      (node (ref "U1") (pin "K4") (pinfunction "VCCIO2_K4") (pintype "power_in"))
      (node (ref "U1") (pin "M4") (pinfunction "VCCIO2_M4") (pintype "power_in"))
      (node (ref "U1") (pin "N4") (pinfunction "VCCIO2_N4") (pintype "power_in"))
    )
    (net (code "143") (name "VCCIO3") (class "Default")
      (node (ref "U1") (pin "R6") (pinfunction "VCCIO3_R6") (pintype "power_in"))
      (node (ref "U1") (pin "R7") (pinfunction "VCCIO3_R7") (pintype "power_in"))
      (node (ref "U1") (pin "R9") (pinfunction "VCCIO3_R9") (pintype "power_in"))
    )
    (net (code "144") (name "VCCIO4") (class "Default")
      (node (ref "U1") (pin "R10") (pinfunction "VCCIO4_R10") (pintype "power_in"))
      (node (ref "U1") (pin "R12") (pinfunction "VCCIO4_R12") (pintype "power_in"))
      (node (ref "U1") (pin "R14") (pinfunction "VCCIO4_R14") (pintype "power_in"))
    )
    (net (code "145") (name "VCCIO5") (class "Default")
      (node (ref "U1") (pin "K15") (pinfunction "VCCIO5_K15") (pintype "power_in"))
      (node (ref "U1") (pin "M15") (pinfunction "VCCIO5_M15") (pintype "power_in"))
      (node (ref "U1") (pin "R15") (pinfunction "VCCIO5_R15") (pintype "power_in"))
    )
    (net (code "146") (name "VCCIO6") (class "Default")
      (node (ref "U1") (pin "F16") (pinfunction "VCCIO6_F16") (pintype "power_in"))
      (node (ref "U1") (pin "G15") (pinfunction "VCCIO6_G15") (pintype "power_in"))
      (node (ref "U1") (pin "J15") (pinfunction "VCCIO6_J15") (pintype "power_in"))
    )
    (net (code "147") (name "VCCIO7") (class "Default")
      (node (ref "U1") (pin "D11") (pinfunction "VCCIO7_D11") (pintype "power_in"))
      (node (ref "U1") (pin "D13") (pinfunction "VCCIO7_D13") (pintype "power_in"))
      (node (ref "U1") (pin "D15") (pinfunction "VCCIO7_D15") (pintype "power_in"))
    )
    (net (code "148") (name "VCCIO8") (class "Default")
      (node (ref "U1") (pin "D4") (pinfunction "VCCIO8_D4") (pintype "power_in"))
      (node (ref "U1") (pin "D6") (pinfunction "VCCIO8_D6") (pintype "power_in"))
      (node (ref "U1") (pin "D8") (pinfunction "VCCIO8_D8") (pintype "power_in"))
    )
    (net (code "149") (name "unconnected-(U1B-IO,_(DM3L{slash}BWS#3L){slash}(DM1L1{slash}BWS#1L1)-PadR4)") (class "Default")
      (node (ref "U1") (pin "R4") (pinfunction "IO,_(DM3L/BWS#3L)/(DM1L1/BWS#1L1)_R4") (pintype "bidirectional"))
    )
    (net (code "150") (name "unconnected-(U1B-IO,_(DQ3L){slash}(DQ1L)-PadR2)") (class "Default")
      (node (ref "U1") (pin "R2") (pinfunction "IO,_(DQ3L)/(DQ1L)_R2") (pintype "bidirectional"))
    )
    (net (code "151") (name "unconnected-(U1B-IO,_DIFFIO_L44n,_(DQ3L){slash}(DQ1L)-PadP1)") (class "Default")
      (node (ref "U1") (pin "P1") (pinfunction "IO,_DIFFIO_L44n,_(DQ3L)/(DQ1L)_P1") (pintype "bidirectional"))
    )
    (net (code "152") (name "unconnected-(U1B-IO,_DIFFIO_L44p,_(DQ3L){slash}(DQ1L)-PadP2)") (class "Default")
      (node (ref "U1") (pin "P2") (pinfunction "IO,_DIFFIO_L44p,_(DQ3L)/(DQ1L)_P2") (pintype "bidirectional"))
    )
    (net (code "153") (name "unconnected-(U1B-IO,_DIFFIO_L52n,_(DQ3L){slash}(DQ1L)-PadR3)") (class "Default")
      (node (ref "U1") (pin "R3") (pinfunction "IO,_DIFFIO_L52n,_(DQ3L)/(DQ1L)_R3") (pintype "bidirectional"))
    )
    (net (code "154") (name "unconnected-(U1B-IO,_DIFFIO_L52p,_(DQ3L){slash}(DQ1L)-PadT3)") (class "Default")
      (node (ref "U1") (pin "T3") (pinfunction "IO,_DIFFIO_L52p,_(DQ3L)/(DQ1L)_T3") (pintype "bidirectional"))
    )
    (net (code "155") (name "unconnected-(U1B-IO,_RDN1-PadT1)") (class "Default")
      (node (ref "U1") (pin "T1") (pinfunction "IO,_RDN1_T1") (pintype "bidirectional"))
    )
    (net (code "156") (name "unconnected-(U1B-IO,_RUP1-PadT2)") (class "Default")
      (node (ref "U1") (pin "T2") (pinfunction "IO,_RUP1_T2") (pintype "bidirectional"))
    )
    (net (code "157") (name "unconnected-(U1B-IO,_VREFB2N2-PadR1)") (class "Default")
      (node (ref "U1") (pin "R1") (pinfunction "IO,_VREFB2N2_R1") (pintype "bidirectional"))
    )
    (net (code "158") (name "unconnected-(U1B-IO,_VREFB2N3-PadR5)") (class "Default")
      (node (ref "U1") (pin "R5") (pinfunction "IO,_VREFB2N3_R5") (pintype "bidirectional"))
    )
    (net (code "159") (name "unconnected-(U1C-IO,_(DQ3B){slash}(DQ5B)-PadP9)") (class "Default")
      (node (ref "U1") (pin "P9") (pinfunction "IO,_(DQ3B)/(DQ5B)_P9") (pintype "bidirectional"))
    )
    (net (code "160") (name "unconnected-(U1C-IO,_(DQS1B{slash}CQ1B#,CDPCLK2){slash}(DQS1B{slash}CQ1B#,CDPCLK2)-PadP6)") (class "Default")
      (node (ref "U1") (pin "P6") (pinfunction "IO,_(DQS1B/CQ1B#,CDPCLK2)/(DQS1B/CQ1B#,CDPCLK2)_P6") (pintype "bidirectional"))
    )
    (net (code "161") (name "unconnected-(U1C-IO,_DIFFIO_B1n-PadV1)") (class "Default")
      (node (ref "U1") (pin "V1") (pinfunction "IO,_DIFFIO_B1n_V1") (pintype "bidirectional"))
    )
    (net (code "162") (name "unconnected-(U1C-IO,_DIFFIO_B1p-PadU1)") (class "Default")
      (node (ref "U1") (pin "U1") (pinfunction "IO,_DIFFIO_B1p_U1") (pintype "bidirectional"))
    )
    (net (code "163") (name "unconnected-(U1C-IO,_DIFFIO_B16n,_(DM3B{slash}BWS#3B){slash}(DM5B1{slash}BWS#5B1)-PadV3)") (class "Default")
      (node (ref "U1") (pin "V3") (pinfunction "IO,_DIFFIO_B16n,_(DM3B/BWS#3B)/(DM5B1/BWS#5B1)_V3") (pintype "bidirectional"))
    )
    (net (code "164") (name "unconnected-(U1C-IO,_DIFFIO_B16p,_(DQS3B{slash}CQ3B#,DPCLK2){slash}(DQS3B{slash}CQ3B#,DPCLK2)-PadU3)") (class "Default")
      (node (ref "U1") (pin "U3") (pinfunction "IO,_DIFFIO_B16p,_(DQS3B/CQ3B#,DPCLK2)/(DQS3B/CQ3B#,DPCLK2)_U3") (pintype "bidirectional"))
    )
    (net (code "165") (name "unconnected-(U1C-IO,_DIFFIO_B17n,_(DQ3B){slash}(DQ5B)-PadV4)") (class "Default")
      (node (ref "U1") (pin "V4") (pinfunction "IO,_DIFFIO_B17n,_(DQ3B)/(DQ5B)_V4") (pintype "bidirectional"))
    )
    (net (code "166") (name "unconnected-(U1C-IO,_DIFFIO_B17p,_(DQ3B){slash}(DQ5B)-PadU4)") (class "Default")
      (node (ref "U1") (pin "U4") (pinfunction "IO,_DIFFIO_B17p,_(DQ3B)/(DQ5B)_U4") (pintype "bidirectional"))
    )
    (net (code "167") (name "unconnected-(U1C-IO,_DIFFIO_B18n,_(DQ3B){slash}(DQ5B)-PadV5)") (class "Default")
      (node (ref "U1") (pin "V5") (pinfunction "IO,_DIFFIO_B18n,_(DQ3B)/(DQ5B)_V5") (pintype "bidirectional"))
    )
    (net (code "168") (name "unconnected-(U1C-IO,_DIFFIO_B18p-PadU5)") (class "Default")
      (node (ref "U1") (pin "U5") (pinfunction "IO,_DIFFIO_B18p_U5") (pintype "bidirectional"))
    )
    (net (code "169") (name "unconnected-(U1C-IO,_DIFFIO_B21n,_(DQS5B{slash}CQ5B#,DPCLK3){slash}(DQS5B{slash}CQ5B#,DPCLK3)-PadT8)") (class "Default")
      (node (ref "U1") (pin "T8") (pinfunction "IO,_DIFFIO_B21n,_(DQS5B/CQ5B#,DPCLK3)/(DQS5B/CQ5B#,DPCLK3)_T8") (pintype "bidirectional"))
    )
    (net (code "170") (name "unconnected-(U1C-IO,_DIFFIO_B21p,_(DQ3B){slash}(DQ5B)-PadR8)") (class "Default")
      (node (ref "U1") (pin "R8") (pinfunction "IO,_DIFFIO_B21p,_(DQ3B)/(DQ5B)_R8") (pintype "bidirectional"))
    )
    (net (code "171") (name "unconnected-(U1C-IO,_DIFFIO_B24n,_(DQ3B){slash}(DQ5B)-PadV6)") (class "Default")
      (node (ref "U1") (pin "V6") (pinfunction "IO,_DIFFIO_B24n,_(DQ3B)/(DQ5B)_V6") (pintype "bidirectional"))
    )
    (net (code "172") (name "unconnected-(U1C-IO,_DIFFIO_B24p,_(DQ3B){slash}(DQ5B)-PadU6)") (class "Default")
      (node (ref "U1") (pin "U6") (pinfunction "IO,_DIFFIO_B24p,_(DQ3B)/(DQ5B)_U6") (pintype "bidirectional"))
    )
    (net (code "173") (name "unconnected-(U1C-IO,_DIFFIO_B26n,_(DQ3B){slash}(DQ5B)-PadV7)") (class "Default")
      (node (ref "U1") (pin "V7") (pinfunction "IO,_DIFFIO_B26n,_(DQ3B)/(DQ5B)_V7") (pintype "bidirectional"))
    )
    (net (code "174") (name "unconnected-(U1C-IO,_DIFFIO_B26p-PadU7)") (class "Default")
      (node (ref "U1") (pin "U7") (pinfunction "IO,_DIFFIO_B26p_U7") (pintype "bidirectional"))
    )
    (net (code "175") (name "unconnected-(U1C-IO,_DIFFIO_B27n,_(DM5B{slash}BWS#5B){slash}(DM5B0{slash}BWS#5B0)-PadV8)") (class "Default")
      (node (ref "U1") (pin "V8") (pinfunction "IO,_DIFFIO_B27n,_(DM5B/BWS#5B)/(DM5B0/BWS#5B0)_V8") (pintype "bidirectional"))
    )
    (net (code "176") (name "unconnected-(U1C-IO,_DIFFIO_B27p,_(DQ3B){slash}(DQ5B)-PadU8)") (class "Default")
      (node (ref "U1") (pin "U8") (pinfunction "IO,_DIFFIO_B27p,_(DQ3B)/(DQ5B)_U8") (pintype "bidirectional"))
    )
    (net (code "177") (name "unconnected-(U1C-IO,_PLL1_CLKOUTn-PadV2)") (class "Default")
      (node (ref "U1") (pin "V2") (pinfunction "IO,_PLL1_CLKOUTn_V2") (pintype "bidirectional"))
    )
    (net (code "178") (name "unconnected-(U1C-IO,_PLL1_CLKOUTp-PadU2)") (class "Default")
      (node (ref "U1") (pin "U2") (pinfunction "IO,_PLL1_CLKOUTp_U2") (pintype "bidirectional"))
    )
    (net (code "179") (name "unconnected-(U1C-IO,_VREFB3N0-PadP8)") (class "Default")
      (node (ref "U1") (pin "P8") (pinfunction "IO,_VREFB3N0_P8") (pintype "bidirectional"))
    )
    (net (code "180") (name "unconnected-(U1C-IO,_VREFB3N1-PadP7)") (class "Default")
      (node (ref "U1") (pin "P7") (pinfunction "IO,_VREFB3N1_P7") (pintype "bidirectional"))
    )
    (net (code "181") (name "unconnected-(U1C-IO,_VREFB3N2-PadT6)") (class "Default")
      (node (ref "U1") (pin "T6") (pinfunction "IO,_VREFB3N2_T6") (pintype "bidirectional"))
    )
    (net (code "182") (name "unconnected-(U1C-IO,_VREFB3N3-PadT4)") (class "Default")
      (node (ref "U1") (pin "T4") (pinfunction "IO,_VREFB3N3_T4") (pintype "bidirectional"))
    )
    (net (code "183") (name "unconnected-(U1D-IO,_(DQ5B){slash}(DQ5B)-PadR11)") (class "Default")
      (node (ref "U1") (pin "R11") (pinfunction "IO,_(DQ5B)/(DQ5B)_R11") (pintype "bidirectional"))
    )
    (net (code "184") (name "unconnected-(U1D-IO,_(DQ5B){slash}(DQ5B)-PadU12)") (class "Default")
      (node (ref "U1") (pin "U12") (pinfunction "IO,_(DQ5B)/(DQ5B)_U12") (pintype "bidirectional"))
    )
    (net (code "185") (name "unconnected-(U1D-IO,_(DQ5B){slash}(DQ5B)-PadV16)") (class "Default")
      (node (ref "U1") (pin "V16") (pinfunction "IO,_(DQ5B)/(DQ5B)_V16") (pintype "bidirectional"))
    )
    (net (code "186") (name "unconnected-(U1D-IO,_(DQS0B{slash}CQ1B,CDPCLK3){slash}(DQS0B{slash}CQ1B,CDPCLK3)-PadR13)") (class "Default")
      (node (ref "U1") (pin "R13") (pinfunction "IO,_(DQS0B/CQ1B,CDPCLK3)/(DQS0B/CQ1B,CDPCLK3)_R13") (pintype "bidirectional"))
    )
    (net (code "187") (name "unconnected-(U1D-IO,_(DQS2B{slash}CQ3B,DPCLK5){slash}(DQS2B{slash}CQ3B,DPCLK5)-PadP12)") (class "Default")
      (node (ref "U1") (pin "P12") (pinfunction "IO,_(DQS2B/CQ3B,DPCLK5)/(DQS2B/CQ3B,DPCLK5)_P12") (pintype "bidirectional"))
    )
    (net (code "188") (name "unconnected-(U1D-IO,_DIFFIO_B28n-PadV11)") (class "Default")
      (node (ref "U1") (pin "V11") (pinfunction "IO,_DIFFIO_B28n_V11") (pintype "bidirectional"))
    )
    (net (code "189") (name "unconnected-(U1D-IO,_DIFFIO_B28p,_(DQ5B){slash}(DQ5B)-PadU11)") (class "Default")
      (node (ref "U1") (pin "U11") (pinfunction "IO,_DIFFIO_B28p,_(DQ5B)/(DQ5B)_U11") (pintype "bidirectional"))
    )
    (net (code "190") (name "unconnected-(U1D-IO,_DIFFIO_B32n,_(DQS4B{slash}CQ5B,DPCLK4){slash}(DQS4B{slash}CQ5B,DPCLK4)-PadV13)") (class "Default")
      (node (ref "U1") (pin "V13") (pinfunction "IO,_DIFFIO_B32n,_(DQS4B/CQ5B,DPCLK4)/(DQS4B/CQ5B,DPCLK4)_V13") (pintype "bidirectional"))
    )
    (net (code "191") (name "unconnected-(U1D-IO,_DIFFIO_B32p,_(DQ5B){slash}(DQ5B)-PadU13)") (class "Default")
      (node (ref "U1") (pin "U13") (pinfunction "IO,_DIFFIO_B32p,_(DQ5B)/(DQ5B)_U13") (pintype "bidirectional"))
    )
    (net (code "192") (name "unconnected-(U1D-IO,_DIFFIO_B33n-PadP11)") (class "Default")
      (node (ref "U1") (pin "P11") (pinfunction "IO,_DIFFIO_B33n_P11") (pintype "bidirectional"))
    )
    (net (code "193") (name "unconnected-(U1D-IO,_DIFFIO_B33p,_(DQ5B){slash}(DQ5B)-PadP10)") (class "Default")
      (node (ref "U1") (pin "P10") (pinfunction "IO,_DIFFIO_B33p,_(DQ5B)/(DQ5B)_P10") (pintype "bidirectional"))
    )
    (net (code "194") (name "unconnected-(U1D-IO,_DIFFIO_B34n,_(DQ5B){slash}(DQ5B)-PadV14)") (class "Default")
      (node (ref "U1") (pin "V14") (pinfunction "IO,_DIFFIO_B34n,_(DQ5B)/(DQ5B)_V14") (pintype "bidirectional"))
    )
    (net (code "195") (name "unconnected-(U1D-IO,_DIFFIO_B34p,_(DQ5B){slash}(DQ5B)-PadU14)") (class "Default")
      (node (ref "U1") (pin "U14") (pinfunction "IO,_DIFFIO_B34p,_(DQ5B)/(DQ5B)_U14") (pintype "bidirectional"))
    )
    (net (code "196") (name "unconnected-(U1D-IO,_DIFFIO_B35n,_(DQ5B){slash}(DQ5B)-PadV15)") (class "Default")
      (node (ref "U1") (pin "V15") (pinfunction "IO,_DIFFIO_B35n,_(DQ5B)/(DQ5B)_V15") (pintype "bidirectional"))
    )
    (net (code "197") (name "unconnected-(U1D-IO,_DIFFIO_B35p-PadU15)") (class "Default")
      (node (ref "U1") (pin "U15") (pinfunction "IO,_DIFFIO_B35p_U15") (pintype "bidirectional"))
    )
    (net (code "198") (name "unconnected-(U1D-IO,_DIFFIO_B47n-PadV17)") (class "Default")
      (node (ref "U1") (pin "V17") (pinfunction "IO,_DIFFIO_B47n_V17") (pintype "bidirectional"))
    )
    (net (code "199") (name "unconnected-(U1D-IO,_DIFFIO_B47p-PadU17)") (class "Default")
      (node (ref "U1") (pin "U17") (pinfunction "IO,_DIFFIO_B47p_U17") (pintype "bidirectional"))
    )
    (net (code "200") (name "unconnected-(U1D-IO,_PLL4_CLKOUTn-PadV18)") (class "Default")
      (node (ref "U1") (pin "V18") (pinfunction "IO,_PLL4_CLKOUTn_V18") (pintype "bidirectional"))
    )
    (net (code "201") (name "unconnected-(U1D-IO,_PLL4_CLKOUTp-PadU18)") (class "Default")
      (node (ref "U1") (pin "U18") (pinfunction "IO,_PLL4_CLKOUTp_U18") (pintype "bidirectional"))
    )
    (net (code "202") (name "unconnected-(U1D-IO,_RDN2-PadT14)") (class "Default")
      (node (ref "U1") (pin "T14") (pinfunction "IO,_RDN2_T14") (pintype "bidirectional"))
    )
    (net (code "203") (name "unconnected-(U1D-IO,_RUP2-PadT13)") (class "Default")
      (node (ref "U1") (pin "T13") (pinfunction "IO,_RUP2_T13") (pintype "bidirectional"))
    )
    (net (code "204") (name "unconnected-(U1D-IO,_VREFB4N0-PadP13)") (class "Default")
      (node (ref "U1") (pin "P13") (pinfunction "IO,_VREFB4N0_P13") (pintype "bidirectional"))
    )
    (net (code "205") (name "unconnected-(U1D-IO,_VREFB4N1-PadU16)") (class "Default")
      (node (ref "U1") (pin "U16") (pinfunction "IO,_VREFB4N1_U16") (pintype "bidirectional"))
    )
    (net (code "206") (name "unconnected-(U1D-IO,_VREFB4N2-PadT11)") (class "Default")
      (node (ref "U1") (pin "T11") (pinfunction "IO,_VREFB4N2_T11") (pintype "bidirectional"))
    )
    (net (code "207") (name "unconnected-(U1D-IO,_VREFB4N3-PadV12)") (class "Default")
      (node (ref "U1") (pin "V12") (pinfunction "IO,_VREFB4N3_V12") (pintype "bidirectional"))
    )
    (net (code "208") (name "unconnected-(U1E-IO,_(DM3R{slash}BWS#3R){slash}(DM1R1{slash}BWS#1R1)-PadN15)") (class "Default")
      (node (ref "U1") (pin "N15") (pinfunction "IO,_(DM3R/BWS#3R)/(DM1R1/BWS#1R1)_N15") (pintype "bidirectional"))
    )
    (net (code "209") (name "unconnected-(U1E-IO,_(DQ3R){slash}(DQ1R)-PadT17)") (class "Default")
      (node (ref "U1") (pin "T17") (pinfunction "IO,_(DQ3R)/(DQ1R)_T17") (pintype "bidirectional"))
    )
    (net (code "210") (name "unconnected-(U1E-IO,_(DQS3R{slash}CQ3R#,CDPCLK4){slash}(DQS3R{slash}CQ3R#,CDPCLK4)-PadT18)") (class "Default")
      (node (ref "U1") (pin "T18") (pinfunction "IO,_(DQS3R/CQ3R#,CDPCLK4)/(DQS3R/CQ3R#,CDPCLK4)_T18") (pintype "bidirectional"))
    )
    (net (code "211") (name "unconnected-(U1E-IO,_DIFFIO_R42n,_(DQ3R){slash}(DQ1R)-PadP18)") (class "Default")
      (node (ref "U1") (pin "P18") (pinfunction "IO,_DIFFIO_R42n,_(DQ3R)/(DQ1R)_P18") (pintype "bidirectional"))
    )
    (net (code "212") (name "unconnected-(U1E-IO,_DIFFIO_R42p,_(DQ3R){slash}(DQ1R)-PadP17)") (class "Default")
      (node (ref "U1") (pin "P17") (pinfunction "IO,_DIFFIO_R42p,_(DQ3R)/(DQ1R)_P17") (pintype "bidirectional"))
    )
    (net (code "213") (name "unconnected-(U1E-IO,_RDN3-PadR16)") (class "Default")
      (node (ref "U1") (pin "R16") (pinfunction "IO,_RDN3_R16") (pintype "bidirectional"))
    )
    (net (code "214") (name "unconnected-(U1E-IO,_RUP3,_(DQ3R){slash}(DQ1R)-PadT16)") (class "Default")
      (node (ref "U1") (pin "T16") (pinfunction "IO,_RUP3,_(DQ3R)/(DQ1R)_T16") (pintype "bidirectional"))
    )
    (net (code "215") (name "unconnected-(U1E-IO,_VREFB5N1-PadN16)") (class "Default")
      (node (ref "U1") (pin "N16") (pinfunction "IO,_VREFB5N1_N16") (pintype "bidirectional"))
    )
    (net (code "216") (name "unconnected-(U1E-IO,_VREFB5N2-PadR17)") (class "Default")
      (node (ref "U1") (pin "R17") (pinfunction "IO,_VREFB5N2_R17") (pintype "bidirectional"))
    )
    (net (code "217") (name "unconnected-(U1E-IO,_VREFB5N3-PadR18)") (class "Default")
      (node (ref "U1") (pin "R18") (pinfunction "IO,_VREFB5N3_R18") (pintype "bidirectional"))
    )
    (net (code "218") (name "unconnected-(U1I-CLK2,_DIFFCLK_1p-PadN2)") (class "Default")
      (node (ref "U1") (pin "N2") (pinfunction "CLK2,_DIFFCLK_1p_N2") (pintype "input"))
    )
    (net (code "219") (name "unconnected-(U1I-CLK6,_DIFFCLK_3p-PadN17)") (class "Default")
      (node (ref "U1") (pin "N17") (pinfunction "CLK6,_DIFFCLK_3p_N17") (pintype "input"))
    )
    (net (code "220") (name "unconnected-(U1I-CLK7,_DIFFCLK_3n-PadN18)") (class "Default")
      (node (ref "U1") (pin "N18") (pinfunction "CLK7,_DIFFCLK_3n_N18") (pintype "input"))
    )
    (net (code "221") (name "unconnected-(U1I-CLK12,_DIFFCLK_7n-PadV10)") (class "Default")
      (node (ref "U1") (pin "V10") (pinfunction "CLK12,_DIFFCLK_7n_V10") (pintype "input"))
    )
    (net (code "222") (name "unconnected-(U1I-CLK13,_DIFFCLK_7p-PadU10)") (class "Default")
      (node (ref "U1") (pin "U10") (pinfunction "CLK13,_DIFFCLK_7p_U10") (pintype "input"))
    )
    (net (code "223") (name "unconnected-(U1I-CLK14,_DIFFCLK_6n-PadV9)") (class "Default")
      (node (ref "U1") (pin "V9") (pinfunction "CLK14,_DIFFCLK_6n_V9") (pintype "input"))
    )
    (net (code "224") (name "unconnected-(U1I-CLK15,_DIFFCLK_6p-PadU9)") (class "Default")
      (node (ref "U1") (pin "U9") (pinfunction "CLK15,_DIFFCLK_6p_U9") (pintype "input"))
    )
  )
)
